# SCH_Acid-Leak_2026-06-09.net
KiCad netlist of a schematic drawn in EasyEDA
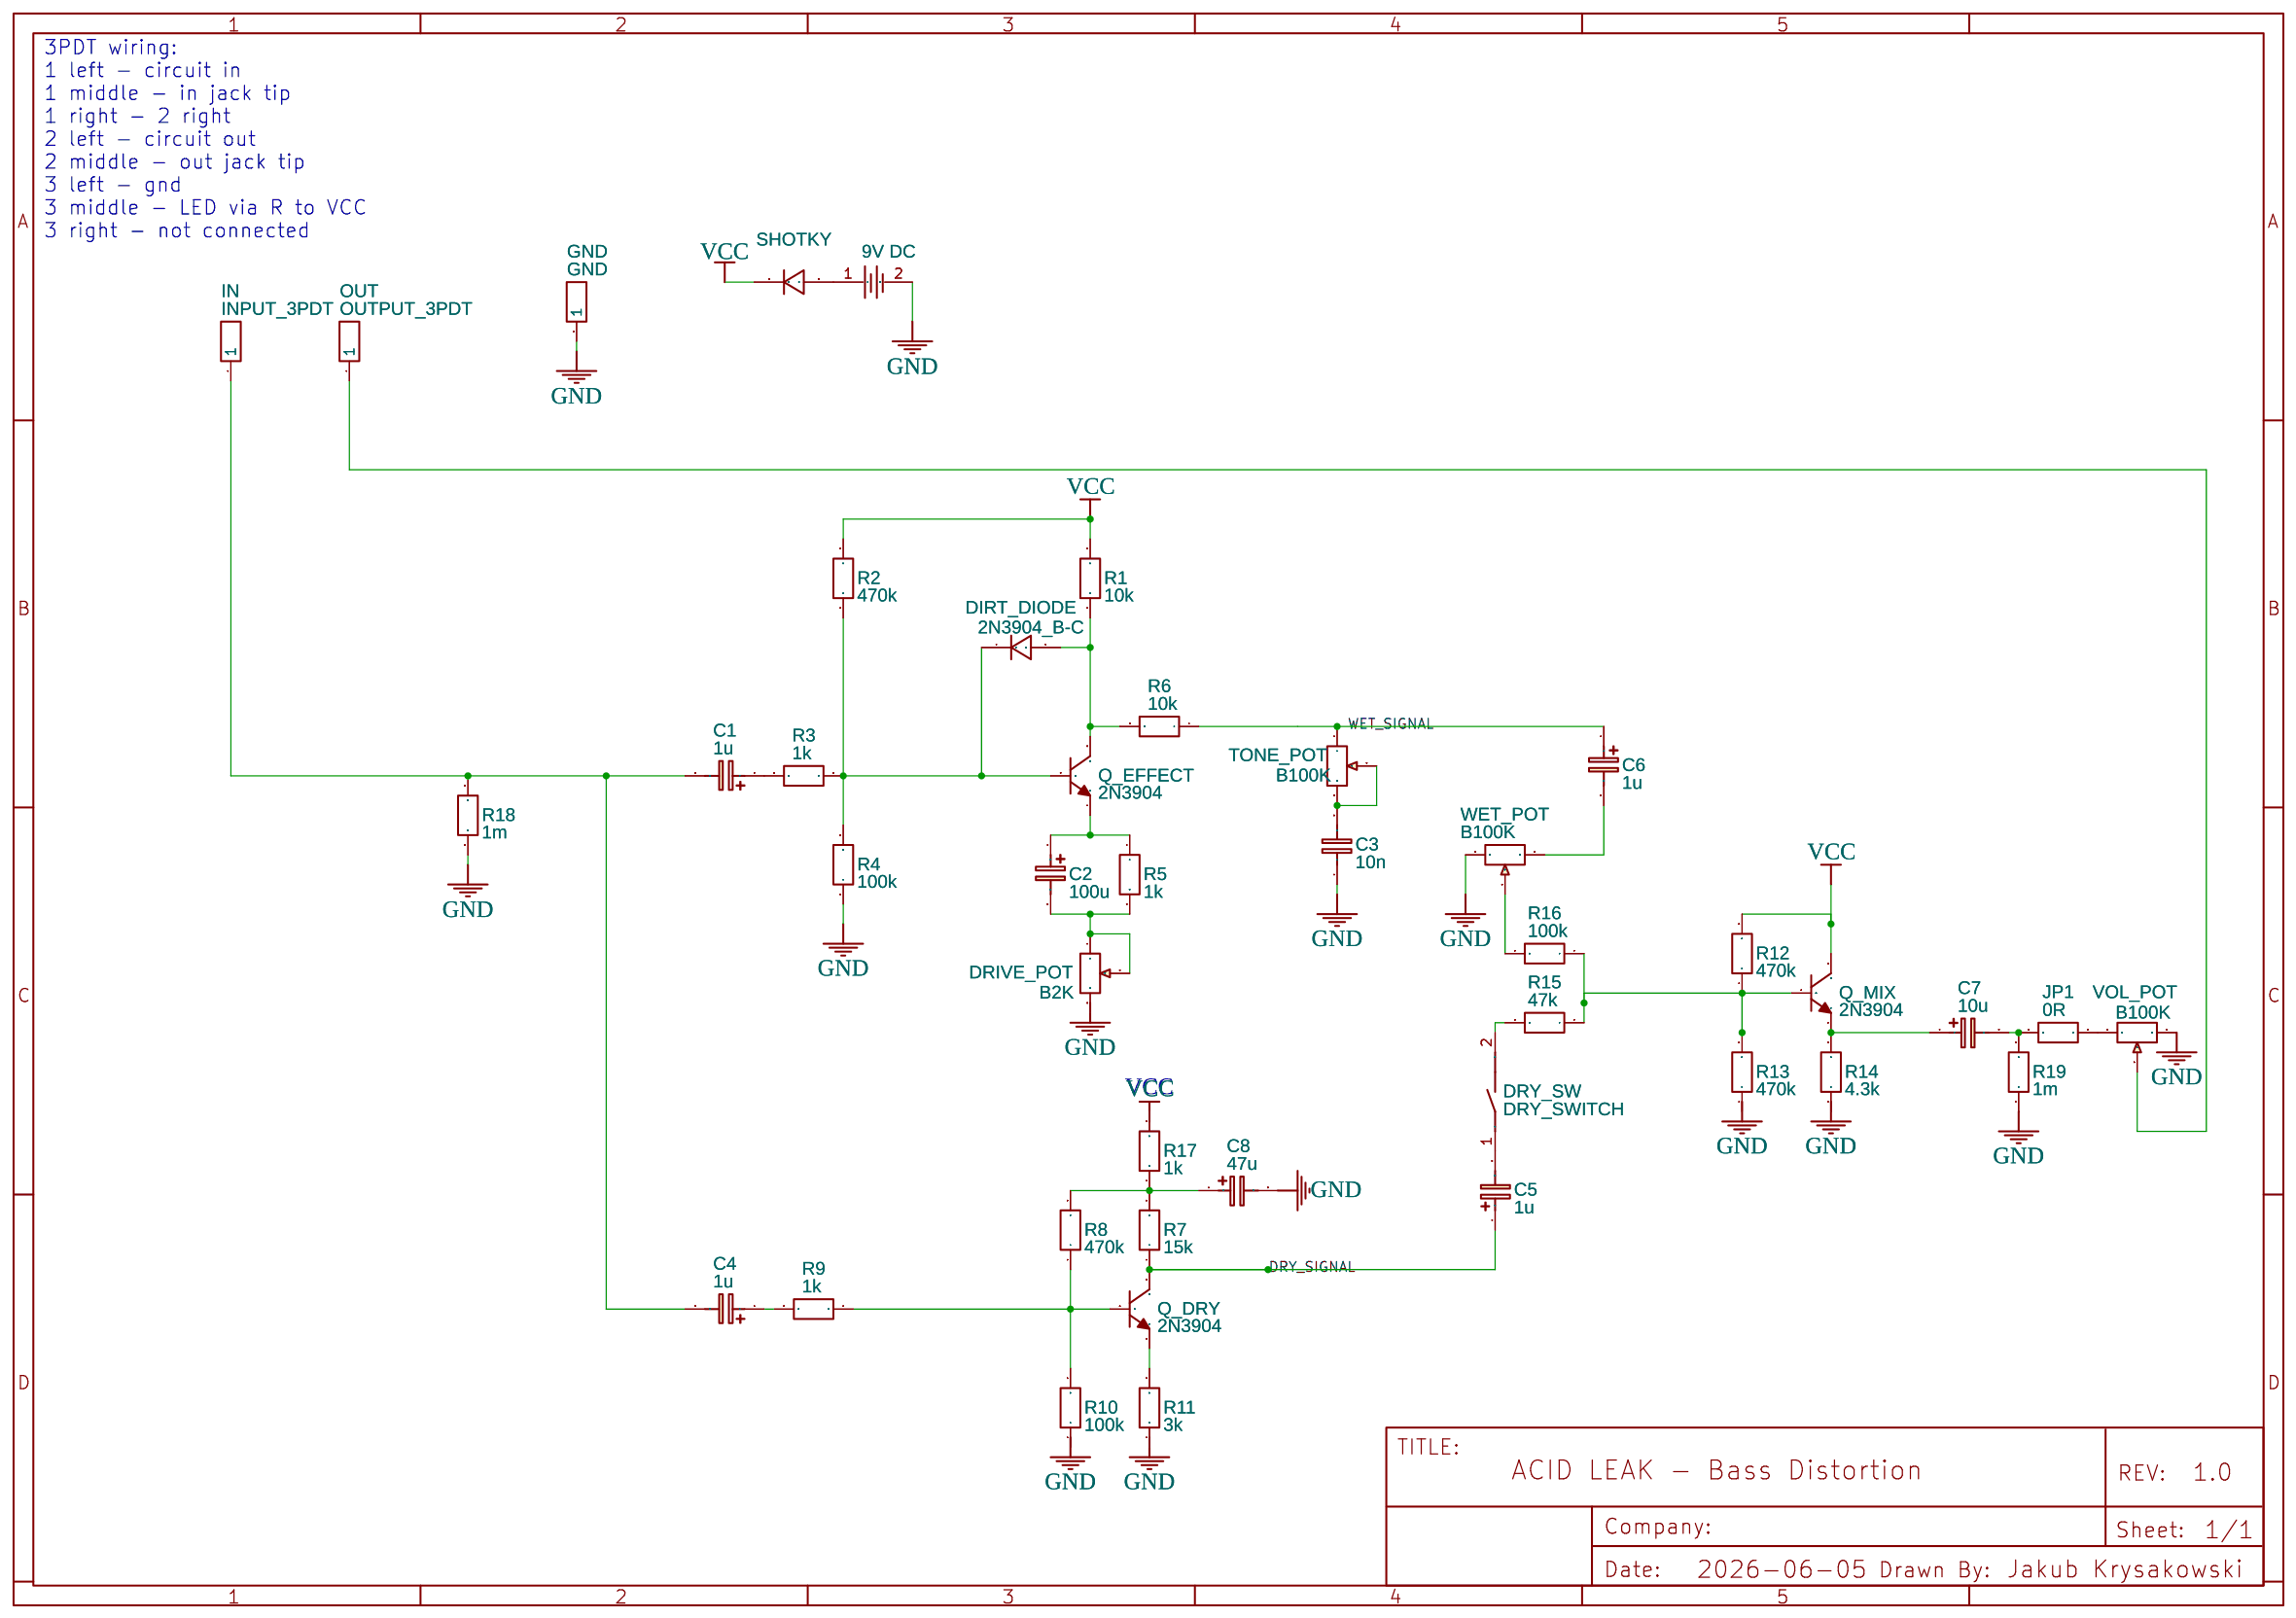
[diagram p0: schematic sheet]

(export (version "E")
  (design (tool "Eeschema 10.0.6"))
  (components
    (comp (ref "C1") (value "1u") (libsource (lib "") (part "CE_TH_D8.0×F3.5_EU_3")))
    (comp (ref "C2") (value "100u") (libsource (lib "") (part "CE_TH_D8.0×F3.5_EU_1")))
    (comp (ref "C3") (value "10n") (libsource (lib "") (part "C_RAD-0.1_EU")))
    (comp (ref "C4") (value "1u") (libsource (lib "") (part "CE_TH_D8.0×F3.5_EU_5")))
    (comp (ref "C5") (value "1u") (libsource (lib "") (part "CE_TH_D8.0×F3.5_EU")))
    (comp (ref "C6") (value "1u") (libsource (lib "") (part "CE_TH_D8.0×F3.5_EU_1")))
    (comp (ref "C7") (value "10u") (libsource (lib "") (part "CE_TH_D8.0×F3.5_EU_2")))
    (comp (ref "C8") (value "47u") (libsource (lib "") (part "CE_TH_D8.0×F3.5_EU_4")))
    (comp (ref "DIRT_DIODE")
      (value "2N3904_B-C")
      (fields (field (name "Manufacturer Part") "1N4148") (field (name "Manufacturer") "STMicroelectronics"))
      (libsource (lib "") (part "1N4148_1"))
    )
    (comp (ref "DRIVE_POT") (value "B2K") (libsource (lib "") (part "R_3296W_EU_3")))
    (comp (ref "DRY_SW")
      (value "DRY_SWITCH")
      (fields (field (name "Manufacturer Part") "DS-1-B-T") (field (name "Manufacturer") "XUNPU(讯普)"))
      (libsource (lib "") (part "DS-1-B-T"))
    )
    (comp (ref "GND") (value "GND") (libsource (lib "") (part "HDR-M-2.54_1x1_1")))
    (comp (ref "IN") (value "INPUT_3PDT") (libsource (lib "") (part "HDR-M-2.54_1x1_2")))
    (comp (ref "JP1") (value "0R") (libsource (lib "") (part "R_0603_EU_2")))
    (comp (ref "OUT") (value "OUTPUT_3PDT") (libsource (lib "") (part "HDR-M-2.54_1x1")))
    (comp (ref "PWR")
      (value "9V DC")
      (fields (field (name "Manufacturer Part") "BS-2-1") (field (name "Manufacturer") "Q&J"))
      (libsource (lib "") (part "CR2032-BS-2-1"))
    )
    (comp (ref "Q_DRY")
      (value "2N3904")
      (fields (field (name "Manufacturer Part") "2n3904S-RTK/PS") (field (name "Manufacturer") "KEC"))
      (libsource (lib "") (part "2N3904(SOT-23)_1"))
    )
    (comp (ref "Q_EFFECT")
      (value "2N3904")
      (fields (field (name "Manufacturer Part") "2n3904S-RTK/PS") (field (name "Manufacturer") "KEC"))
      (libsource (lib "") (part "2N3904(SOT-23)"))
    )
    (comp (ref "Q_MIX")
      (value "2N3904")
      (fields (field (name "Manufacturer Part") "2n3904S-RTK/PS") (field (name "Manufacturer") "KEC"))
      (libsource (lib "") (part "2N3904(SOT-23)_2"))
    )
    (comp (ref "R1") (value "10k") (libsource (lib "") (part "R_0603_EU")))
    (comp (ref "R2") (value "470k") (libsource (lib "") (part "R_0603_EU")))
    (comp (ref "R3") (value "1k") (libsource (lib "") (part "R_0603_EU_3")))
    (comp (ref "R4") (value "100k") (libsource (lib "") (part "R_0603_EU")))
    (comp (ref "R5") (value "1k") (libsource (lib "") (part "R_0603_EU_1")))
    (comp (ref "R6") (value "10k") (libsource (lib "") (part "R_0603_EU_3")))
    (comp (ref "R7") (value "15k") (libsource (lib "") (part "R_0603_EU")))
    (comp (ref "R8") (value "470k") (libsource (lib "") (part "R_0603_EU")))
    (comp (ref "R9") (value "1k") (libsource (lib "") (part "R_0603_EU_3")))
    (comp (ref "R10") (value "100k") (libsource (lib "") (part "R_0603_EU")))
    (comp (ref "R11") (value "3k") (libsource (lib "") (part "R_0603_EU")))
    (comp (ref "R12") (value "470k") (libsource (lib "") (part "R_0603_EU")))
    (comp (ref "R13") (value "470k") (libsource (lib "") (part "R_0603_EU")))
    (comp (ref "R14") (value "4.3k") (libsource (lib "") (part "R_0603_EU")))
    (comp (ref "R15") (value "47k") (libsource (lib "") (part "R_0603_EU_3")))
    (comp (ref "R16") (value "100k") (libsource (lib "") (part "R_0603_EU_3")))
    (comp (ref "R17") (value "1k") (libsource (lib "") (part "R_0603_EU")))
    (comp (ref "R18") (value "1m") (libsource (lib "") (part "R_0603_EU")))
    (comp (ref "R19") (value "1m") (libsource (lib "") (part "R_0603_EU")))
    (comp (ref "SHOTKY")
      (value "Shotky")
      (fields (field (name "Manufacturer Part") "1N4148") (field (name "Manufacturer") "STMicroelectronics"))
      (libsource (lib "") (part "1N4148"))
    )
    (comp (ref "TONE_POT") (value "B100K") (libsource (lib "") (part "R_3296W_EU_2")))
    (comp (ref "VOL_POT") (value "B100K") (libsource (lib "") (part "R_3296W_EU_1")))
    (comp (ref "WET_POT") (value "B100K") (libsource (lib "") (part "R_3296W_EU")))
  )
  (nets
    (net (code "1") (name "/DRY_SIGNAL") (class "Default")
      (node (ref "C5") (pin "1") (pinfunction "1_1") (pintype "unspecified"))
      (node (ref "Q_DRY") (pin "3") (pinfunction "C_3") (pintype "input"))
      (node (ref "R7") (pin "1") (pinfunction "1_1") (pintype "unspecified"))
    )
    (net (code "2") (name "/WET_SIGNAL") (class "Default")
      (node (ref "C6") (pin "1") (pinfunction "1_1") (pintype "unspecified"))
      (node (ref "R6") (pin "1") (pinfunction "1_1") (pintype "unspecified"))
      (node (ref "TONE_POT") (pin "1") (pinfunction "1_1") (pintype "input"))
    )
    (net (code "3") (name "GND") (class "Default")
      (node (ref "C3") (pin "1") (pinfunction "1_1") (pintype "unspecified"))
      (node (ref "C8") (pin "2") (pinfunction "2_2") (pintype "unspecified"))
      (node (ref "DRIVE_POT") (pin "3") (pinfunction "3_3") (pintype "input"))
      (node (ref "GND") (pin "1") (pinfunction "1_1") (pintype "input"))
      (node (ref "PWR") (pin "2") (pinfunction "2_2") (pintype "input"))
      (node (ref "R10") (pin "1") (pinfunction "1_1") (pintype "unspecified"))
      (node (ref "R11") (pin "1") (pinfunction "1_1") (pintype "unspecified"))
      (node (ref "R13") (pin "1") (pinfunction "1_1") (pintype "unspecified"))
      (node (ref "R14") (pin "1") (pinfunction "1_1") (pintype "unspecified"))
      (node (ref "R18") (pin "1") (pinfunction "1_1") (pintype "unspecified"))
      (node (ref "R19") (pin "1") (pinfunction "1_1") (pintype "unspecified"))
      (node (ref "R4") (pin "1") (pinfunction "1_1") (pintype "unspecified"))
      (node (ref "VOL_POT") (pin "1") (pinfunction "1_1") (pintype "input"))
      (node (ref "WET_POT") (pin "3") (pinfunction "3_3") (pintype "input"))
    )
    (net (code "4") (name "Net-(C1-Pad1)") (class "Default")
      (node (ref "C1") (pin "1") (pinfunction "1_1") (pintype "unspecified"))
      (node (ref "R3") (pin "2") (pinfunction "2_2") (pintype "unspecified"))
    )
    (net (code "5") (name "Net-(C1-Pad2)") (class "Default")
      (node (ref "C1") (pin "2") (pinfunction "2_2") (pintype "unspecified"))
      (node (ref "C4") (pin "2") (pinfunction "2_2") (pintype "unspecified"))
      (node (ref "IN") (pin "1") (pinfunction "1_1") (pintype "input"))
      (node (ref "R18") (pin "2") (pinfunction "2_2") (pintype "unspecified"))
    )
    (net (code "6") (name "Net-(C2-Pad2)") (class "Default")
      (node (ref "C2") (pin "2") (pinfunction "2_2") (pintype "unspecified"))
      (node (ref "DRIVE_POT") (pin "1") (pinfunction "1_1") (pintype "input"))
      (node (ref "DRIVE_POT") (pin "2") (pinfunction "2_2") (pintype "input"))
      (node (ref "R5") (pin "2") (pinfunction "2_2") (pintype "unspecified"))
    )
    (net (code "7") (name "Net-(C3-Pad2)") (class "Default")
      (node (ref "C3") (pin "2") (pinfunction "2_2") (pintype "unspecified"))
      (node (ref "TONE_POT") (pin "2") (pinfunction "2_2") (pintype "input"))
      (node (ref "TONE_POT") (pin "3") (pinfunction "3_3") (pintype "input"))
    )
    (net (code "8") (name "Net-(C4-Pad1)") (class "Default")
      (node (ref "C4") (pin "1") (pinfunction "1_1") (pintype "unspecified"))
      (node (ref "R9") (pin "2") (pinfunction "2_2") (pintype "unspecified"))
    )
    (net (code "9") (name "Net-(C5-Pad2)") (class "Default")
      (node (ref "C5") (pin "2") (pinfunction "2_2") (pintype "unspecified"))
      (node (ref "DRY_SW") (pin "1") (pinfunction "1_1") (pintype "unspecified"))
    )
    (net (code "10") (name "Net-(C6-Pad2)") (class "Default")
      (node (ref "C6") (pin "2") (pinfunction "2_2") (pintype "unspecified"))
      (node (ref "WET_POT") (pin "1") (pinfunction "1_1") (pintype "input"))
    )
    (net (code "11") (name "Net-(C7-Pad2)") (class "Default")
      (node (ref "C7") (pin "2") (pinfunction "2_2") (pintype "unspecified"))
      (node (ref "JP1") (pin "2") (pinfunction "2_2") (pintype "unspecified"))
      (node (ref "R19") (pin "2") (pinfunction "2_2") (pintype "unspecified"))
    )
    (net (code "12") (name "Net-(C8-Pad1)") (class "Default")
      (node (ref "C8") (pin "1") (pinfunction "1_1") (pintype "unspecified"))
      (node (ref "R17") (pin "1") (pinfunction "1_1") (pintype "unspecified"))
      (node (ref "R7") (pin "2") (pinfunction "2_2") (pintype "unspecified"))
      (node (ref "R8") (pin "2") (pinfunction "2_2") (pintype "unspecified"))
    )
    (net (code "13") (name "Net-(DRY_SW-Pad2)") (class "Default")
      (node (ref "DRY_SW") (pin "2") (pinfunction "2_2") (pintype "unspecified"))
      (node (ref "R15") (pin "2") (pinfunction "2_2") (pintype "unspecified"))
    )
    (net (code "14") (name "Net-(JP1-Pad1)") (class "Default")
      (node (ref "JP1") (pin "1") (pinfunction "1_1") (pintype "unspecified"))
      (node (ref "VOL_POT") (pin "3") (pinfunction "3_3") (pintype "input"))
    )
    (net (code "15") (name "Net-(OUT-Pad1)") (class "Default")
      (node (ref "OUT") (pin "1") (pinfunction "1_1") (pintype "input"))
      (node (ref "VOL_POT") (pin "2") (pinfunction "2_2") (pintype "input"))
    )
    (net (code "16") (name "Net-(PWR-Pad1)") (class "Default")
      (node (ref "PWR") (pin "1") (pinfunction "1_1") (pintype "input"))
      (node (ref "SHOTKY") (pin "2") (pinfunction "2_2") (pintype "unspecified"))
    )
    (net (code "17") (name "Net-(Q_DRY-B)") (class "Default")
      (node (ref "Q_DRY") (pin "2") (pinfunction "B_2") (pintype "input"))
      (node (ref "R10") (pin "2") (pinfunction "2_2") (pintype "unspecified"))
      (node (ref "R8") (pin "1") (pinfunction "1_1") (pintype "unspecified"))
      (node (ref "R9") (pin "1") (pinfunction "1_1") (pintype "unspecified"))
    )
    (net (code "18") (name "Net-(Q_DRY-E)") (class "Default")
      (node (ref "Q_DRY") (pin "1") (pinfunction "E_1") (pintype "input"))
      (node (ref "R11") (pin "2") (pinfunction "2_2") (pintype "unspecified"))
    )
    (net (code "19") (name "Net-(Q_EFFECT-B)") (class "Default")
      (node (ref "DIRT_DIODE") (pin "1") (pinfunction "1_1") (pintype "unspecified"))
      (node (ref "Q_EFFECT") (pin "2") (pinfunction "B_2") (pintype "input"))
      (node (ref "R2") (pin "1") (pinfunction "1_1") (pintype "unspecified"))
      (node (ref "R3") (pin "1") (pinfunction "1_1") (pintype "unspecified"))
      (node (ref "R4") (pin "2") (pinfunction "2_2") (pintype "unspecified"))
    )
    (net (code "20") (name "Net-(Q_EFFECT-C)") (class "Default")
      (node (ref "DIRT_DIODE") (pin "2") (pinfunction "2_2") (pintype "unspecified"))
      (node (ref "Q_EFFECT") (pin "3") (pinfunction "C_3") (pintype "input"))
      (node (ref "R1") (pin "1") (pinfunction "1_1") (pintype "unspecified"))
      (node (ref "R6") (pin "2") (pinfunction "2_2") (pintype "unspecified"))
    )
    (net (code "21") (name "Net-(Q_EFFECT-E)") (class "Default")
      (node (ref "C2") (pin "1") (pinfunction "1_1") (pintype "unspecified"))
      (node (ref "Q_EFFECT") (pin "1") (pinfunction "E_1") (pintype "input"))
      (node (ref "R5") (pin "1") (pinfunction "1_1") (pintype "unspecified"))
    )
    (net (code "22") (name "Net-(Q_MIX-B)") (class "Default")
      (node (ref "Q_MIX") (pin "2") (pinfunction "B_2") (pintype "input"))
      (node (ref "R12") (pin "1") (pinfunction "1_1") (pintype "unspecified"))
      (node (ref "R13") (pin "2") (pinfunction "2_2") (pintype "unspecified"))
      (node (ref "R15") (pin "1") (pinfunction "1_1") (pintype "unspecified"))
      (node (ref "R16") (pin "1") (pinfunction "1_1") (pintype "unspecified"))
    )
    (net (code "23") (name "Net-(Q_MIX-E)") (class "Default")
      (node (ref "C7") (pin "1") (pinfunction "1_1") (pintype "unspecified"))
      (node (ref "Q_MIX") (pin "1") (pinfunction "E_1") (pintype "input"))
      (node (ref "R14") (pin "2") (pinfunction "2_2") (pintype "unspecified"))
    )
    (net (code "24") (name "Net-(R16-Pad2)") (class "Default")
      (node (ref "R16") (pin "2") (pinfunction "2_2") (pintype "unspecified"))
      (node (ref "WET_POT") (pin "2") (pinfunction "2_2") (pintype "input"))
    )
    (net (code "25") (name "VCC") (class "Default")
      (node (ref "Q_MIX") (pin "3") (pinfunction "C_3") (pintype "input"))
      (node (ref "R1") (pin "2") (pinfunction "2_2") (pintype "unspecified"))
      (node (ref "R12") (pin "2") (pinfunction "2_2") (pintype "unspecified"))
      (node (ref "R17") (pin "2") (pinfunction "2_2") (pintype "unspecified"))
      (node (ref "R2") (pin "2") (pinfunction "2_2") (pintype "unspecified"))
      (node (ref "SHOTKY") (pin "1") (pinfunction "1_1") (pintype "unspecified"))
    )
  )
)
